# plantGrowthLeds_4chnl.net
KiCad netlist of a schematic drawn in Altium Designer
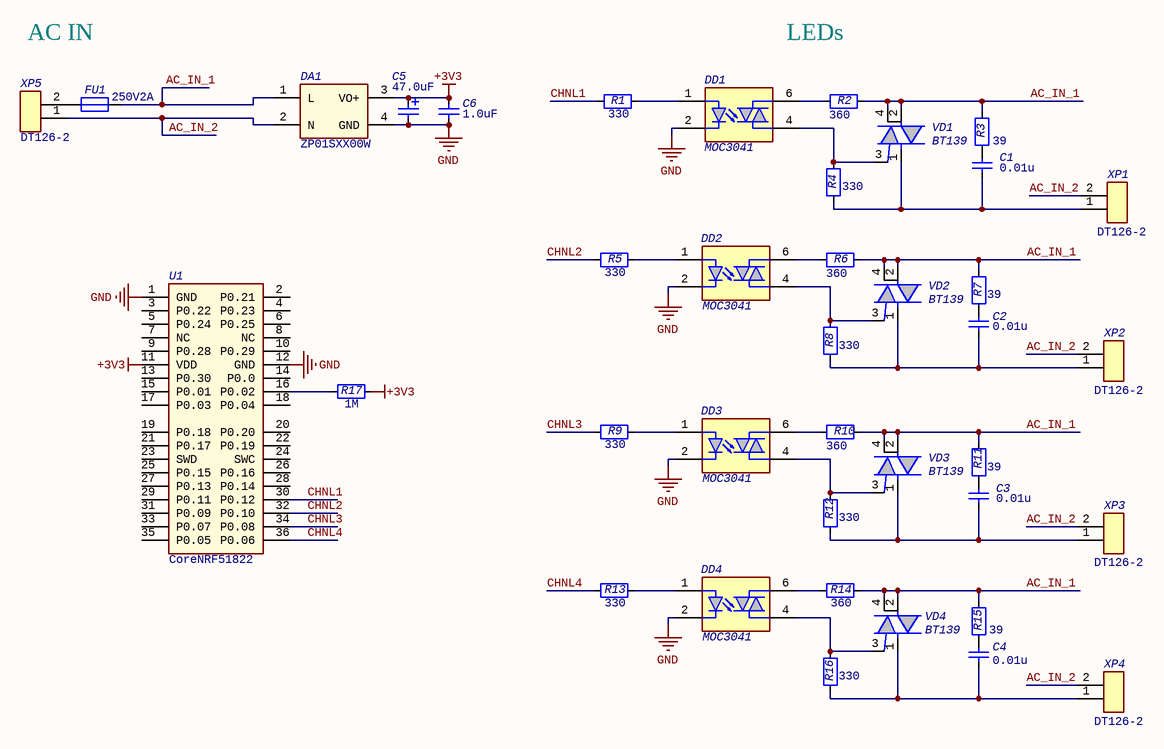
[diagram p0: plantGrowthLeds_4chnl.SchDoc]

(export (version "E")
  (design (tool "Eeschema 10.0.6"))
  (components
    (comp (ref "C1")
      (value "0.01u")
      (footprint "C1206")
      (description "Capacitor Chip 1206, Non-Polarized")
      (libsource (lib "Kpada") (part "C1206"))
    )
    (comp (ref "C2")
      (value "0.01u")
      (footprint "C1206")
      (description "Capacitor Chip 1206, Non-Polarized")
      (libsource (lib "Kpada") (part "C1206"))
    )
    (comp (ref "C3")
      (value "0.01u")
      (footprint "C1206")
      (description "Capacitor Chip 1206, Non-Polarized")
      (libsource (lib "Kpada") (part "C1206"))
    )
    (comp (ref "C4")
      (value "0.01u")
      (footprint "C1206")
      (description "Capacitor Chip 1206, Non-Polarized")
      (libsource (lib "Kpada") (part "C1206"))
    )
    (comp (ref "C5")
      (value "47.0uF")
      (footprint "C_B_COMPACT")
      (description "Capacitor Polarized Tantalum, B-Size")
      (libsource (lib "Kpada") (part "Cap_Ta_B-Size"))
    )
    (comp (ref "C6")
      (value "1.0uF")
      (footprint "C0805_COMPACT")
      (description "Capacitor Chip 0805, Non-Polarized")
      (libsource (lib "Kpada") (part "C0805"))
    )
    (comp (ref "DA1")
      (value "ZP01SXX00W")
      (footprint "ZP01SXX0W")
      (description "AC-DC 1W Single Output Converter")
      (libsource (lib "Kpada") (part "ZP01SXX00W"))
    )
    (comp (ref "DD1")
      (value "MOC3041")
      (footprint "DIP6")
      (description "Optoisolators Triac Driver Output 400V")
      (libsource (lib "Kpada_lib") (part "MOC3041"))
    )
    (comp (ref "DD2")
      (value "MOC3041")
      (footprint "DIP6")
      (description "Optoisolators Triac Driver Output 400V")
      (libsource (lib "Kpada") (part "MOC3041"))
    )
    (comp (ref "DD3")
      (value "MOC3041")
      (footprint "DIP6")
      (description "Optoisolators Triac Driver Output 400V")
      (libsource (lib "Kpada") (part "MOC3041"))
    )
    (comp (ref "DD4")
      (value "MOC3041")
      (footprint "DIP6")
      (description "Optoisolators Triac Driver Output 400V")
      (libsource (lib "Kpada") (part "MOC3041"))
    )
    (comp (ref "FU1")
      (value "250V2A")
      (footprint "FUSE_20x5mm_GLASS")
      (description "Fuse Board")
      (fields (field (name "Comment") "FUSE_BOARD"))
      (libsource (lib "Kpada") (part "FUSE_BOARD"))
    )
    (comp (ref "R1")
      (value "330")
      (footprint "R0805_COMPACT")
      (description "Resistor Chip 0805")
      (libsource (lib "Kpada") (part "R0805"))
    )
    (comp (ref "R2")
      (value "360")
      (footprint "R1206")
      (description "Resistor Chip 1206")
      (libsource (lib "Kpada") (part "R1206"))
    )
    (comp (ref "R3")
      (value "39")
      (footprint "R1206")
      (description "Resistor Chip 1206")
      (libsource (lib "Kpada") (part "R1206"))
    )
    (comp (ref "R4")
      (value "330")
      (footprint "R1206")
      (description "Resistor Chip 1206")
      (libsource (lib "Kpada") (part "R1206"))
    )
    (comp (ref "R5")
      (value "330")
      (footprint "R0805_COMPACT")
      (description "Resistor Chip 0805")
      (libsource (lib "Kpada") (part "R0805"))
    )
    (comp (ref "R6")
      (value "360")
      (footprint "R1206")
      (description "Resistor Chip 1206")
      (libsource (lib "Kpada") (part "R1206"))
    )
    (comp (ref "R7")
      (value "39")
      (footprint "R1206")
      (description "Resistor Chip 1206")
      (libsource (lib "Kpada") (part "R1206"))
    )
    (comp (ref "R8")
      (value "330")
      (footprint "R1206")
      (description "Resistor Chip 1206")
      (libsource (lib "Kpada") (part "R1206"))
    )
    (comp (ref "R9")
      (value "330")
      (footprint "R0805_COMPACT")
      (description "Resistor Chip 0805")
      (libsource (lib "Kpada") (part "R0805"))
    )
    (comp (ref "R10")
      (value "360")
      (footprint "R1206")
      (description "Resistor Chip 1206")
      (libsource (lib "Kpada") (part "R1206"))
    )
    (comp (ref "R11")
      (value "39")
      (footprint "R1206")
      (description "Resistor Chip 1206")
      (libsource (lib "Kpada") (part "R1206"))
    )
    (comp (ref "R12")
      (value "330")
      (footprint "R1206")
      (description "Resistor Chip 1206")
      (libsource (lib "Kpada") (part "R1206"))
    )
    (comp (ref "R13")
      (value "330")
      (footprint "R0805_COMPACT")
      (description "Resistor Chip 0805")
      (libsource (lib "Kpada") (part "R0805"))
    )
    (comp (ref "R14")
      (value "360")
      (footprint "R1206")
      (description "Resistor Chip 1206")
      (libsource (lib "Kpada") (part "R1206"))
    )
    (comp (ref "R15")
      (value "39")
      (footprint "R1206")
      (description "Resistor Chip 1206")
      (libsource (lib "Kpada") (part "R1206"))
    )
    (comp (ref "R16")
      (value "330")
      (footprint "R1206")
      (description "Resistor Chip 1206")
      (libsource (lib "Kpada") (part "R1206"))
    )
    (comp (ref "R17")
      (value "1M")
      (footprint "R0805_COMPACT")
      (description "Resistor Chip 0805")
      (libsource (lib "Kpada") (part "R0805"))
    )
    (comp (ref "U1")
      (value "CoreNRF51822")
      (footprint "BOARD_CORE_NRF51822")
      (description "board Core NRF51822")
      (libsource (lib "Kpada") (part "CoreNRF51822"))
    )
    (comp (ref "VD1")
      (value "BT139")
      (footprint "TO220-lie")
      (description "Triac")
      (libsource (lib "Kpada_lib") (part "BT139_HEAT"))
    )
    (comp (ref "VD2")
      (value "BT139")
      (footprint "TO220-lie")
      (description "Triac")
      (libsource (lib "Kpada") (part "BT139"))
    )
    (comp (ref "VD3")
      (value "BT139")
      (footprint "TO220-lie")
      (description "Triac")
      (libsource (lib "Kpada") (part "BT139"))
    )
    (comp (ref "VD4")
      (value "BT139")
      (footprint "TO220-lie")
      (description "Triac")
      (libsource (lib "Kpada") (part "BT139"))
    )
    (comp (ref "XP1")
      (value "DT126-2")
      (footprint "DT126-2-5mm")
      (description "Screw terminal 2 way 5mm")
      (libsource (lib "") (part "DT126-2_1"))
    )
    (comp (ref "XP2")
      (value "DT126-2")
      (footprint "DT126-2-5mm")
      (description "Screw terminal 2 way 5mm")
      (libsource (lib "") (part "DT126-2_1"))
    )
    (comp (ref "XP3")
      (value "DT126-2")
      (footprint "DT126-2-5mm")
      (description "Screw terminal 2 way 5mm")
      (libsource (lib "") (part "DT126-2_1"))
    )
    (comp (ref "XP4")
      (value "DT126-2")
      (footprint "DT126-2-5mm")
      (description "Screw terminal 2 way 5mm")
      (libsource (lib "") (part "DT126-2_1"))
    )
    (comp (ref "XP5")
      (value "DT126-2")
      (footprint "DT126-2-5mm")
      (description "Screw terminal 2 way 5mm")
      (libsource (lib "Kpada") (part "DT126-2"))
    )
  )
  (nets
    (net (code "1") (name "+3V3") (class "Default")
      (node (ref "C5") (pin "1") (pinfunction "P_1") (pintype "passive"))
      (node (ref "C6") (pin "2") (pinfunction "M_2") (pintype "passive"))
      (node (ref "DA1") (pin "3") (pinfunction "VO+_3") (pintype "power_in"))
      (node (ref "R17") (pin "2") (pinfunction "2_2") (pintype "passive"))
      (node (ref "U1") (pin "11") (pinfunction "VDD_11") (pintype "passive"))
    )
    (net (code "2") (name "/AC_IN_1") (class "Default")
      (node (ref "DA1") (pin "1") (pinfunction "L_1") (pintype "power_in"))
      (node (ref "FU1") (pin "1") (pinfunction "1_1") (pintype "passive"))
      (node (ref "R10") (pin "2") (pinfunction "2_2") (pintype "passive"))
      (node (ref "R11") (pin "2") (pinfunction "2_2") (pintype "passive"))
      (node (ref "R14") (pin "2") (pinfunction "2_2") (pintype "passive"))
      (node (ref "R15") (pin "2") (pinfunction "2_2") (pintype "passive"))
      (node (ref "R2") (pin "2") (pinfunction "2_2") (pintype "passive"))
      (node (ref "R3") (pin "2") (pinfunction "2_2") (pintype "passive"))
      (node (ref "R6") (pin "2") (pinfunction "2_2") (pintype "passive"))
      (node (ref "R7") (pin "2") (pinfunction "2_2") (pintype "passive"))
      (node (ref "VD1") (pin "2") (pinfunction "T2_2") (pintype "passive"))
      (node (ref "VD1") (pin "4") (pinfunction "HEAT_4") (pintype "passive"))
      (node (ref "VD2") (pin "2") (pinfunction "T2_2") (pintype "passive"))
      (node (ref "VD2") (pin "4") (pinfunction "HEAT_4") (pintype "passive"))
      (node (ref "VD3") (pin "2") (pinfunction "T2_2") (pintype "passive"))
      (node (ref "VD3") (pin "4") (pinfunction "HEAT_4") (pintype "passive"))
      (node (ref "VD4") (pin "2") (pinfunction "T2_2") (pintype "passive"))
      (node (ref "VD4") (pin "4") (pinfunction "HEAT_4") (pintype "passive"))
    )
    (net (code "3") (name "/AC_IN_2") (class "Default")
      (node (ref "DA1") (pin "2") (pinfunction "N_2") (pintype "power_in"))
      (node (ref "XP1") (pin "2") (pinfunction "2_2") (pintype "passive"))
      (node (ref "XP2") (pin "2") (pinfunction "2_2") (pintype "passive"))
      (node (ref "XP3") (pin "2") (pinfunction "2_2") (pintype "passive"))
      (node (ref "XP4") (pin "2") (pinfunction "2_2") (pintype "passive"))
      (node (ref "XP5") (pin "1") (pinfunction "1_1") (pintype "passive"))
    )
    (net (code "4") (name "/CHNL1") (class "Default")
      (node (ref "R1") (pin "1") (pinfunction "1_1") (pintype "passive"))
      (node (ref "U1") (pin "30") (pinfunction "P0.12_30") (pintype "passive"))
    )
    (net (code "5") (name "/CHNL2") (class "Default")
      (node (ref "R5") (pin "1") (pinfunction "1_1") (pintype "passive"))
      (node (ref "U1") (pin "32") (pinfunction "P0.10_32") (pintype "passive"))
    )
    (net (code "6") (name "/CHNL3") (class "Default")
      (node (ref "R9") (pin "1") (pinfunction "1_1") (pintype "passive"))
      (node (ref "U1") (pin "34") (pinfunction "P0.08_34") (pintype "passive"))
    )
    (net (code "7") (name "/CHNL4") (class "Default")
      (node (ref "R13") (pin "1") (pinfunction "1_1") (pintype "passive"))
      (node (ref "U1") (pin "36") (pinfunction "P0.06_36") (pintype "passive"))
    )
    (net (code "8") (name "GND") (class "Default")
      (node (ref "C5") (pin "2") (pinfunction "M_2") (pintype "passive"))
      (node (ref "C6") (pin "1") (pinfunction "P_1") (pintype "passive"))
      (node (ref "DA1") (pin "4") (pinfunction "GND_4") (pintype "power_in"))
      (node (ref "DD1") (pin "2") (pinfunction "GND_2") (pintype "passive"))
      (node (ref "DD2") (pin "2") (pinfunction "GND_2") (pintype "passive"))
      (node (ref "DD3") (pin "2") (pinfunction "GND_2") (pintype "passive"))
      (node (ref "DD4") (pin "2") (pinfunction "GND_2") (pintype "passive"))
      (node (ref "U1") (pin "1") (pinfunction "GND_1") (pintype "passive"))
      (node (ref "U1") (pin "12") (pinfunction "GND_12") (pintype "passive"))
    )
    (net (code "9") (name "Net-(C1-M)") (class "Default")
      (node (ref "C1") (pin "2") (pinfunction "M_2") (pintype "passive"))
      (node (ref "R3") (pin "1") (pinfunction "1_1") (pintype "passive"))
    )
    (net (code "10") (name "Net-(C1-P)") (class "Default")
      (node (ref "C1") (pin "1") (pinfunction "P_1") (pintype "passive"))
      (node (ref "R4") (pin "1") (pinfunction "1_1") (pintype "passive"))
      (node (ref "VD1") (pin "1") (pinfunction "T1_1") (pintype "passive"))
      (node (ref "XP1") (pin "1") (pinfunction "1_1") (pintype "passive"))
    )
    (net (code "11") (name "Net-(C2-M)") (class "Default")
      (node (ref "C2") (pin "2") (pinfunction "M_2") (pintype "passive"))
      (node (ref "R7") (pin "1") (pinfunction "1_1") (pintype "passive"))
    )
    (net (code "12") (name "Net-(C2-P)") (class "Default")
      (node (ref "C2") (pin "1") (pinfunction "P_1") (pintype "passive"))
      (node (ref "R8") (pin "1") (pinfunction "1_1") (pintype "passive"))
      (node (ref "VD2") (pin "1") (pinfunction "T1_1") (pintype "passive"))
      (node (ref "XP2") (pin "1") (pinfunction "1_1") (pintype "passive"))
    )
    (net (code "13") (name "Net-(C3-M)") (class "Default")
      (node (ref "C3") (pin "2") (pinfunction "M_2") (pintype "passive"))
      (node (ref "R11") (pin "1") (pinfunction "1_1") (pintype "passive"))
    )
    (net (code "14") (name "Net-(C3-P)") (class "Default")
      (node (ref "C3") (pin "1") (pinfunction "P_1") (pintype "passive"))
      (node (ref "R12") (pin "1") (pinfunction "1_1") (pintype "passive"))
      (node (ref "VD3") (pin "1") (pinfunction "T1_1") (pintype "passive"))
      (node (ref "XP3") (pin "1") (pinfunction "1_1") (pintype "passive"))
    )
    (net (code "15") (name "Net-(C4-M)") (class "Default")
      (node (ref "C4") (pin "2") (pinfunction "M_2") (pintype "passive"))
      (node (ref "R15") (pin "1") (pinfunction "1_1") (pintype "passive"))
    )
    (net (code "16") (name "Net-(C4-P)") (class "Default")
      (node (ref "C4") (pin "1") (pinfunction "P_1") (pintype "passive"))
      (node (ref "R16") (pin "1") (pinfunction "1_1") (pintype "passive"))
      (node (ref "VD4") (pin "1") (pinfunction "T1_1") (pintype "passive"))
      (node (ref "XP4") (pin "1") (pinfunction "1_1") (pintype "passive"))
    )
    (net (code "17") (name "Net-(DD1-MT-Pad6)") (class "Default")
      (node (ref "DD1") (pin "6") (pinfunction "MT_6") (pintype "passive"))
      (node (ref "R2") (pin "1") (pinfunction "1_1") (pintype "passive"))
    )
    (net (code "18") (name "Net-(DD1-VCC)") (class "Default")
      (node (ref "DD1") (pin "1") (pinfunction "VCC_1") (pintype "passive"))
      (node (ref "R1") (pin "2") (pinfunction "2_2") (pintype "passive"))
    )
    (net (code "19") (name "Net-(DD2-MT-Pad6)") (class "Default")
      (node (ref "DD2") (pin "6") (pinfunction "MT_6") (pintype "passive"))
      (node (ref "R6") (pin "1") (pinfunction "1_1") (pintype "passive"))
    )
    (net (code "20") (name "Net-(DD2-VCC)") (class "Default")
      (node (ref "DD2") (pin "1") (pinfunction "VCC_1") (pintype "passive"))
      (node (ref "R5") (pin "2") (pinfunction "2_2") (pintype "passive"))
    )
    (net (code "21") (name "Net-(DD3-MT-Pad6)") (class "Default")
      (node (ref "DD3") (pin "6") (pinfunction "MT_6") (pintype "passive"))
      (node (ref "R10") (pin "1") (pinfunction "1_1") (pintype "passive"))
    )
    (net (code "22") (name "Net-(DD3-VCC)") (class "Default")
      (node (ref "DD3") (pin "1") (pinfunction "VCC_1") (pintype "passive"))
      (node (ref "R9") (pin "2") (pinfunction "2_2") (pintype "passive"))
    )
    (net (code "23") (name "Net-(DD4-MT-Pad6)") (class "Default")
      (node (ref "DD4") (pin "6") (pinfunction "MT_6") (pintype "passive"))
      (node (ref "R14") (pin "1") (pinfunction "1_1") (pintype "passive"))
    )
    (net (code "24") (name "Net-(DD4-VCC)") (class "Default")
      (node (ref "DD4") (pin "1") (pinfunction "VCC_1") (pintype "passive"))
      (node (ref "R13") (pin "2") (pinfunction "2_2") (pintype "passive"))
    )
    (net (code "25") (name "Net-(FU1-Pad2)") (class "Default")
      (node (ref "FU1") (pin "2") (pinfunction "2_2") (pintype "passive"))
      (node (ref "XP5") (pin "2") (pinfunction "2_2") (pintype "passive"))
    )
    (net (code "26") (name "Net-(U1-P0.02)") (class "Default")
      (node (ref "R17") (pin "1") (pinfunction "1_1") (pintype "passive"))
      (node (ref "U1") (pin "16") (pinfunction "P0.02_16") (pintype "passive"))
    )
    (net (code "27") (name "Net-(VD1-G)") (class "Default")
      (node (ref "DD1") (pin "4") (pinfunction "MT_4") (pintype "passive"))
      (node (ref "R4") (pin "2") (pinfunction "2_2") (pintype "passive"))
      (node (ref "VD1") (pin "3") (pinfunction "G_3") (pintype "passive"))
    )
    (net (code "28") (name "Net-(VD2-G)") (class "Default")
      (node (ref "DD2") (pin "4") (pinfunction "MT_4") (pintype "passive"))
      (node (ref "R8") (pin "2") (pinfunction "2_2") (pintype "passive"))
      (node (ref "VD2") (pin "3") (pinfunction "G_3") (pintype "passive"))
    )
    (net (code "29") (name "Net-(VD3-G)") (class "Default")
      (node (ref "DD3") (pin "4") (pinfunction "MT_4") (pintype "passive"))
      (node (ref "R12") (pin "2") (pinfunction "2_2") (pintype "passive"))
      (node (ref "VD3") (pin "3") (pinfunction "G_3") (pintype "passive"))
    )
    (net (code "30") (name "Net-(VD4-G)") (class "Default")
      (node (ref "DD4") (pin "4") (pinfunction "MT_4") (pintype "passive"))
      (node (ref "R16") (pin "2") (pinfunction "2_2") (pintype "passive"))
      (node (ref "VD4") (pin "3") (pinfunction "G_3") (pintype "passive"))
    )
    (net (code "31") (name "unconnected-(U1-NC-Pad7)") (class "Default")
      (node (ref "U1") (pin "7") (pinfunction "NC_7") (pintype "passive"))
    )
    (net (code "32") (name "unconnected-(U1-NC-Pad8)") (class "Default")
      (node (ref "U1") (pin "8") (pinfunction "NC_8") (pintype "passive"))
    )
    (net (code "33") (name "unconnected-(U1-P0.0-Pad14)") (class "Default")
      (node (ref "U1") (pin "14") (pinfunction "P0.0_14") (pintype "passive"))
    )
    (net (code "34") (name "unconnected-(U1-P0.01-Pad15)") (class "Default")
      (node (ref "U1") (pin "15") (pinfunction "P0.01_15") (pintype "passive"))
    )
    (net (code "35") (name "unconnected-(U1-P0.03-Pad17)") (class "Default")
      (node (ref "U1") (pin "17") (pinfunction "P0.03_17") (pintype "passive"))
    )
    (net (code "36") (name "unconnected-(U1-P0.04-Pad18)") (class "Default")
      (node (ref "U1") (pin "18") (pinfunction "P0.04_18") (pintype "passive"))
    )
    (net (code "37") (name "unconnected-(U1-P0.05-Pad35)") (class "Default")
      (node (ref "U1") (pin "35") (pinfunction "P0.05_35") (pintype "passive"))
    )
    (net (code "38") (name "unconnected-(U1-P0.07-Pad33)") (class "Default")
      (node (ref "U1") (pin "33") (pinfunction "P0.07_33") (pintype "passive"))
    )
    (net (code "39") (name "unconnected-(U1-P0.09-Pad31)") (class "Default")
      (node (ref "U1") (pin "31") (pinfunction "P0.09_31") (pintype "passive"))
    )
    (net (code "40") (name "unconnected-(U1-P0.11-Pad29)") (class "Default")
      (node (ref "U1") (pin "29") (pinfunction "P0.11_29") (pintype "passive"))
    )
    (net (code "41") (name "unconnected-(U1-P0.13-Pad27)") (class "Default")
      (node (ref "U1") (pin "27") (pinfunction "P0.13_27") (pintype "passive"))
    )
    (net (code "42") (name "unconnected-(U1-P0.14-Pad28)") (class "Default")
      (node (ref "U1") (pin "28") (pinfunction "P0.14_28") (pintype "passive"))
    )
    (net (code "43") (name "unconnected-(U1-P0.15-Pad25)") (class "Default")
      (node (ref "U1") (pin "25") (pinfunction "P0.15_25") (pintype "passive"))
    )
    (net (code "44") (name "unconnected-(U1-P0.16-Pad26)") (class "Default")
      (node (ref "U1") (pin "26") (pinfunction "P0.16_26") (pintype "passive"))
    )
    (net (code "45") (name "unconnected-(U1-P0.17-Pad21)") (class "Default")
      (node (ref "U1") (pin "21") (pinfunction "P0.17_21") (pintype "passive"))
    )
    (net (code "46") (name "unconnected-(U1-P0.18-Pad19)") (class "Default")
      (node (ref "U1") (pin "19") (pinfunction "P0.18_19") (pintype "passive"))
    )
    (net (code "47") (name "unconnected-(U1-P0.19-Pad22)") (class "Default")
      (node (ref "U1") (pin "22") (pinfunction "P0.19_22") (pintype "passive"))
    )
    (net (code "48") (name "unconnected-(U1-P0.20-Pad20)") (class "Default")
      (node (ref "U1") (pin "20") (pinfunction "P0.20_20") (pintype "passive"))
    )
    (net (code "49") (name "unconnected-(U1-P0.21-Pad2)") (class "Default")
      (node (ref "U1") (pin "2") (pinfunction "P0.21_2") (pintype "passive"))
    )
    (net (code "50") (name "unconnected-(U1-P0.22-Pad3)") (class "Default")
      (node (ref "U1") (pin "3") (pinfunction "P0.22_3") (pintype "passive"))
    )
    (net (code "51") (name "unconnected-(U1-P0.23-Pad4)") (class "Default")
      (node (ref "U1") (pin "4") (pinfunction "P0.23_4") (pintype "passive"))
    )
    (net (code "52") (name "unconnected-(U1-P0.24-Pad5)") (class "Default")
      (node (ref "U1") (pin "5") (pinfunction "P0.24_5") (pintype "passive"))
    )
    (net (code "53") (name "unconnected-(U1-P0.25-Pad6)") (class "Default")
      (node (ref "U1") (pin "6") (pinfunction "P0.25_6") (pintype "passive"))
    )
    (net (code "54") (name "unconnected-(U1-P0.28-Pad9)") (class "Default")
      (node (ref "U1") (pin "9") (pinfunction "P0.28_9") (pintype "passive"))
    )
    (net (code "55") (name "unconnected-(U1-P0.29-Pad10)") (class "Default")
      (node (ref "U1") (pin "10") (pinfunction "P0.29_10") (pintype "passive"))
    )
    (net (code "56") (name "unconnected-(U1-P0.30-Pad13)") (class "Default")
      (node (ref "U1") (pin "13") (pinfunction "P0.30_13") (pintype "passive"))
    )
    (net (code "57") (name "unconnected-(U1-SWC-Pad24)") (class "Default")
      (node (ref "U1") (pin "24") (pinfunction "SWC_24") (pintype "passive"))
    )
    (net (code "58") (name "unconnected-(U1-SWD-Pad23)") (class "Default")
      (node (ref "U1") (pin "23") (pinfunction "SWD_23") (pintype "passive"))
    )
  )
)
